# GPSSDver2.net
KiCad netlist of a schematic drawn in EAGLE
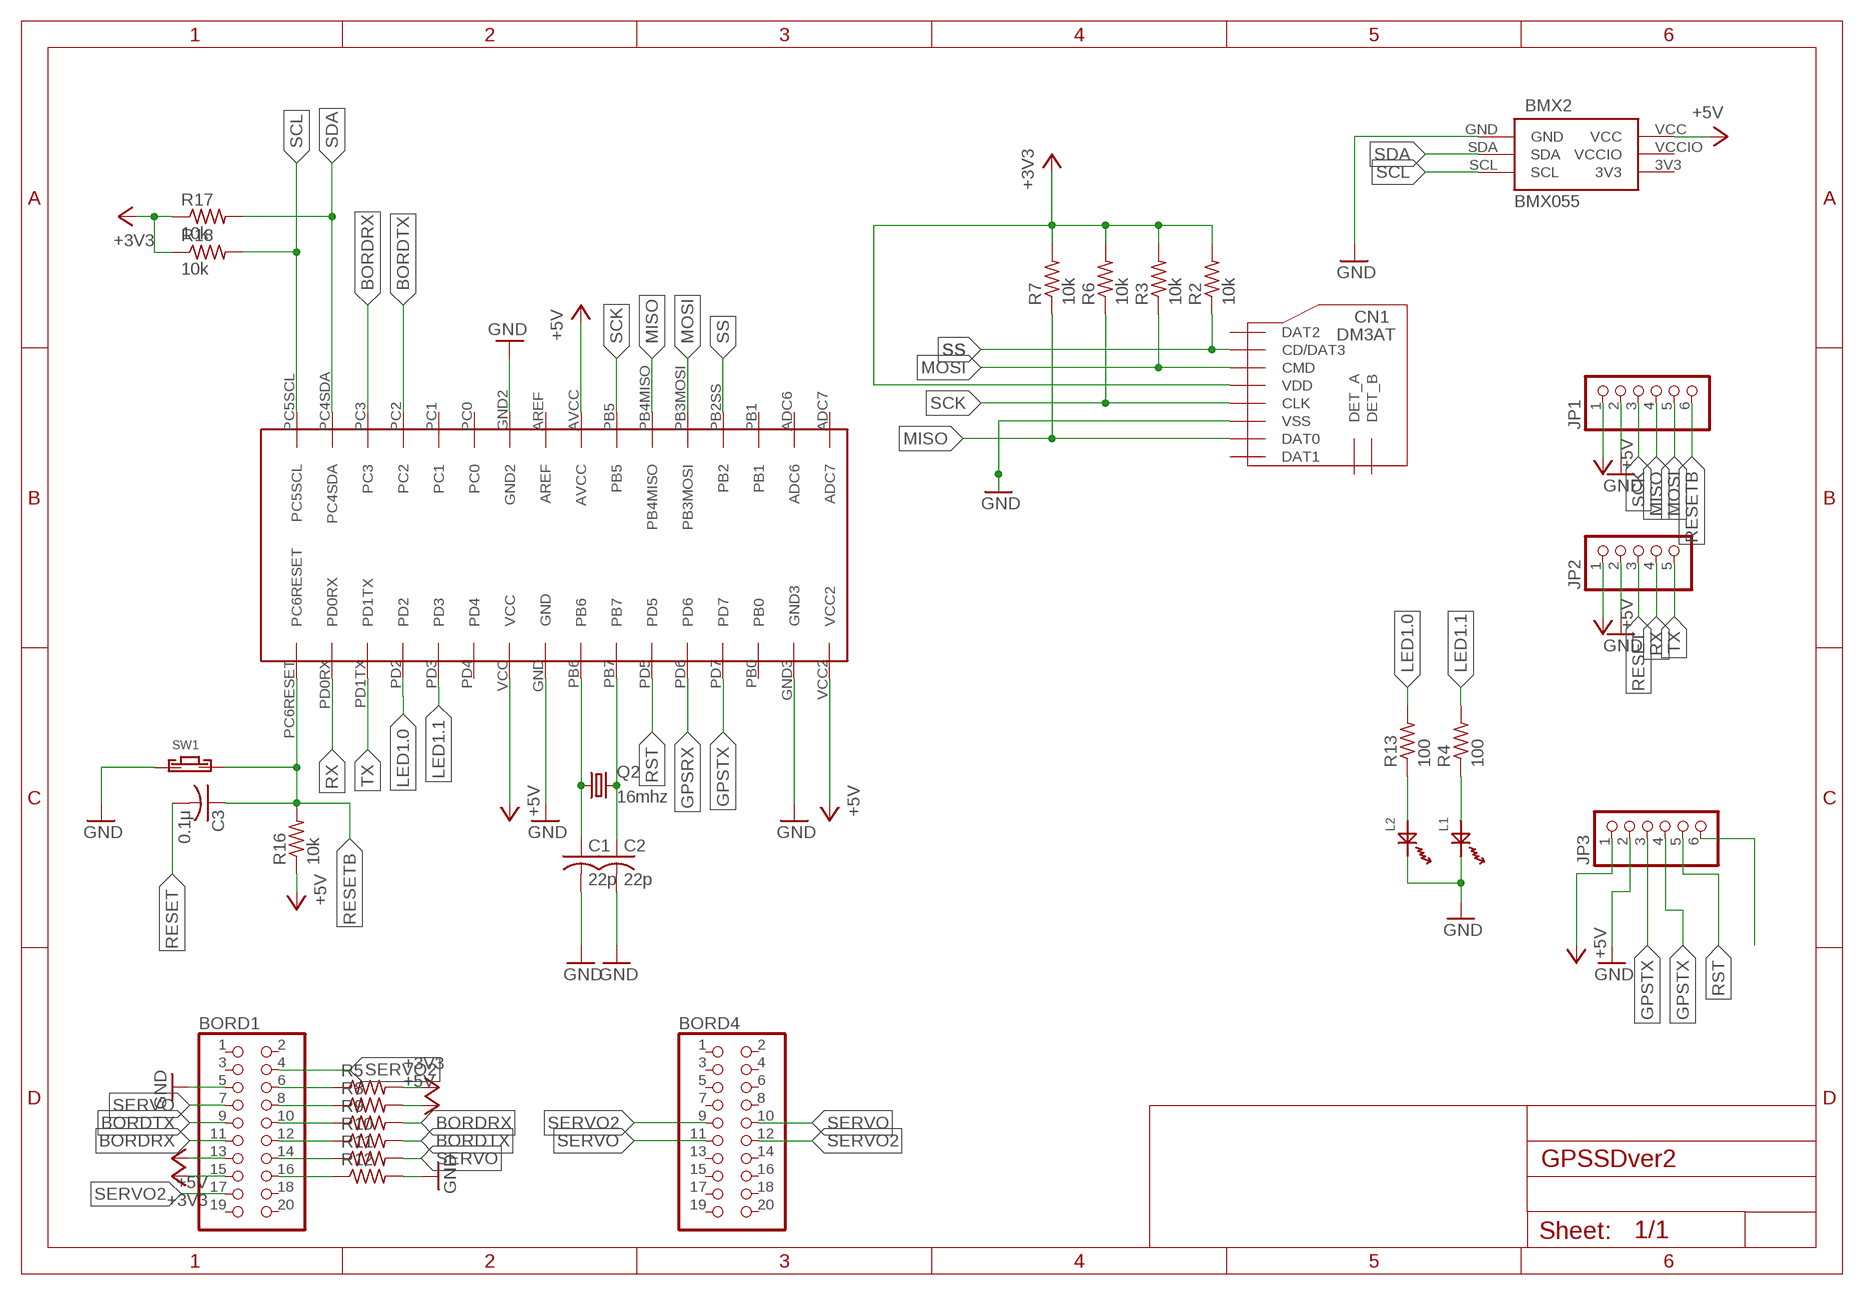
[diagram p0: schematic, sheet 1]

(export (version "E")
  (design (tool "Eeschema 10.0.6"))
  (components
    (comp (ref "BMX2")
      (value "BMX055")
      (footprint "eagle-import:BMX055")
      (libsource (lib "eagle-import") (part "BMX055"))
    )
    (comp (ref "BORD1")
      (value "PINHD-2X10/90")
      (footprint "eagle-import:2X10_90")
      (libsource (lib "eagle-import") (part "PINHD-2X10/90"))
    )
    (comp (ref "BORD4")
      (value "PINHD-2X10/90")
      (footprint "eagle-import:2X10_90")
      (libsource (lib "eagle-import") (part "PINHD-2X10/90"))
    )
    (comp (ref "C1")
      (value "22p")
      (footprint "eagle-import:C1608")
      (libsource (lib "eagle-import") (part "C-USC1608"))
    )
    (comp (ref "C2")
      (value "22p")
      (footprint "eagle-import:C1608")
      (libsource (lib "eagle-import") (part "C-USC1608"))
    )
    (comp (ref "C3")
      (value "0.1μ")
      (footprint "eagle-import:C1608")
      (libsource (lib "eagle-import") (part "C-USC1608"))
    )
    (comp (ref "CN1")
      (value "DM3AT")
      (footprint "eagle-import:DM3AT")
      (libsource (lib "eagle-import") (part "DM3AT"))
    )
    (comp (ref "JP1")
      (value "PINHD-1X6")
      (footprint "eagle-import:1X06")
      (libsource (lib "eagle-import") (part "PINHD-1X6"))
    )
    (comp (ref "JP2")
      (value "PINHD-1X5")
      (footprint "eagle-import:1X05")
      (libsource (lib "eagle-import") (part "PINHD-1X5"))
    )
    (comp (ref "JP3")
      (value "PINHD-1X6")
      (footprint "eagle-import:1X06")
      (libsource (lib "eagle-import") (part "PINHD-1X6"))
    )
    (comp (ref "L1")
      (value "OSXX1608C1A")
      (footprint "eagle-import:OSXX1608C1A")
      (libsource (lib "eagle-import") (part "OSXX1608C1A"))
    )
    (comp (ref "L2")
      (value "OSXX1608C1A")
      (footprint "eagle-import:OSXX1608C1A")
      (libsource (lib "eagle-import") (part "OSXX1608C1A"))
    )
    (comp (ref "Q2")
      (value "16mhz")
      (footprint "eagle-import:HC49UP")
      (libsource (lib "eagle-import") (part "CRYSTALHC49UP"))
    )
    (comp (ref "R2")
      (value "10k")
      (footprint "eagle-import:R0603")
      (libsource (lib "eagle-import") (part "R-US_R0603"))
    )
    (comp (ref "R3")
      (value "10k")
      (footprint "eagle-import:R0603")
      (libsource (lib "eagle-import") (part "R-US_R0603"))
    )
    (comp (ref "R4")
      (value "100")
      (footprint "eagle-import:R0603")
      (libsource (lib "eagle-import") (part "R-US_R0603"))
    )
    (comp (ref "R5")
      (value "R-US_R0603")
      (footprint "eagle-import:R0603")
      (libsource (lib "eagle-import") (part "R-US_R0603"))
    )
    (comp (ref "R6")
      (value "10k")
      (footprint "eagle-import:R0603")
      (libsource (lib "eagle-import") (part "R-US_R0603"))
    )
    (comp (ref "R7")
      (value "10k")
      (footprint "eagle-import:R0603")
      (libsource (lib "eagle-import") (part "R-US_R0603"))
    )
    (comp (ref "R8")
      (value "R-US_R0603")
      (footprint "eagle-import:R0603")
      (libsource (lib "eagle-import") (part "R-US_R0603"))
    )
    (comp (ref "R9")
      (value "R-US_R0603")
      (footprint "eagle-import:R0603")
      (libsource (lib "eagle-import") (part "R-US_R0603"))
    )
    (comp (ref "R10")
      (value "R-US_R0603")
      (footprint "eagle-import:R0603")
      (libsource (lib "eagle-import") (part "R-US_R0603"))
    )
    (comp (ref "R11")
      (value "R-US_R0603")
      (footprint "eagle-import:R0603")
      (libsource (lib "eagle-import") (part "R-US_R0603"))
    )
    (comp (ref "R12")
      (value "R-US_R0603")
      (footprint "eagle-import:R0603")
      (libsource (lib "eagle-import") (part "R-US_R0603"))
    )
    (comp (ref "R13")
      (value "100")
      (footprint "eagle-import:R0603")
      (libsource (lib "eagle-import") (part "R-US_R0603"))
    )
    (comp (ref "R16")
      (value "10k")
      (footprint "eagle-import:R0603")
      (libsource (lib "eagle-import") (part "R-US_R0603"))
    )
    (comp (ref "R17")
      (value "10k")
      (footprint "eagle-import:R0603")
      (libsource (lib "eagle-import") (part "R-US_R0603"))
    )
    (comp (ref "R18")
      (value "10k")
      (footprint "eagle-import:R0603")
      (libsource (lib "eagle-import") (part "R-US_R0603"))
    )
    (comp (ref "SW1")
      (value "TVAF06-A020B-R")
      (footprint "eagle-import:TVAF06-A020B-R")
      (libsource (lib "eagle-import") (part "TVAF06-A020B-R"))
    )
    (comp (ref "U$3")
      (value "ATMEGA328P-AU")
      (footprint "eagle-import:QFP80P900X900X120-32N")
      (libsource (lib "eagle-import") (part "ATMEGA328P-AU"))
    )
  )
  (nets
    (net (code "1") (name "+3V3") (class "Default")
      (node (ref "BORD1") (pin "15") (pinfunction "15_15") (pintype "passive"))
      (node (ref "CN1") (pin "VDD") (pinfunction "VDD_VDD") (pintype "bidirectional"))
      (node (ref "R17") (pin "1") (pinfunction "1_1") (pintype "passive"))
      (node (ref "R18") (pin "1") (pinfunction "1_1") (pintype "passive"))
      (node (ref "R2") (pin "2") (pinfunction "2_2") (pintype "passive"))
      (node (ref "R3") (pin "2") (pinfunction "2_2") (pintype "passive"))
      (node (ref "R5") (pin "2") (pinfunction "2_2") (pintype "passive"))
      (node (ref "R6") (pin "2") (pinfunction "2_2") (pintype "passive"))
      (node (ref "R7") (pin "2") (pinfunction "2_2") (pintype "passive"))
    )
    (net (code "2") (name "+5V") (class "Default")
      (node (ref "BMX2") (pin "VCC") (pinfunction "VCC_VCC") (pintype "power_in"))
      (node (ref "BORD1") (pin "13") (pinfunction "13_13") (pintype "passive"))
      (node (ref "JP1") (pin "1") (pinfunction "1_1") (pintype "passive"))
      (node (ref "JP2") (pin "1") (pinfunction "1_1") (pintype "passive"))
      (node (ref "JP3") (pin "1") (pinfunction "1_1") (pintype "passive"))
      (node (ref "R16") (pin "1") (pinfunction "1_1") (pintype "passive"))
      (node (ref "R8") (pin "2") (pinfunction "2_2") (pintype "passive"))
      (node (ref "U$3") (pin "AVCC") (pinfunction "AVCC_AVCC") (pintype "bidirectional"))
      (node (ref "U$3") (pin "VCC") (pinfunction "VCC_VCC") (pintype "bidirectional"))
      (node (ref "U$3") (pin "VCC2") (pinfunction "VCC2_VCC2") (pintype "bidirectional"))
    )
    (net (code "3") (name "/3V3") (class "Default")
      (node (ref "BMX2") (pin "3V3") (pinfunction "3V3_3V3") (pintype "power_in"))
    )
    (net (code "4") (name "/VCCIO") (class "Default")
      (node (ref "BMX2") (pin "VCCIO") (pinfunction "VCCIO_VCCIO") (pintype "power_in"))
    )
    (net (code "5") (name "BORDRX") (class "Default")
      (node (ref "BORD1") (pin "11") (pinfunction "11_11") (pintype "passive"))
      (node (ref "R9") (pin "2") (pinfunction "2_2") (pintype "passive"))
      (node (ref "U$3") (pin "PC3") (pinfunction "PC3_PC3") (pintype "bidirectional"))
    )
    (net (code "6") (name "BORDTX") (class "Default")
      (node (ref "BORD1") (pin "9") (pinfunction "9_9") (pintype "passive"))
      (node (ref "R10") (pin "2") (pinfunction "2_2") (pintype "passive"))
      (node (ref "U$3") (pin "PC2") (pinfunction "PC2_PC2") (pintype "bidirectional"))
    )
    (net (code "7") (name "GND") (class "Default")
      (node (ref "BMX2") (pin "GND") (pinfunction "GND_GND") (pintype "power_in"))
      (node (ref "BORD1") (pin "5") (pinfunction "5_5") (pintype "passive"))
      (node (ref "C1") (pin "2") (pinfunction "2_2") (pintype "passive"))
      (node (ref "C2") (pin "2") (pinfunction "2_2") (pintype "passive"))
      (node (ref "CN1") (pin "VSS") (pinfunction "VSS_VSS") (pintype "bidirectional"))
      (node (ref "JP1") (pin "2") (pinfunction "2_2") (pintype "passive"))
      (node (ref "JP2") (pin "2") (pinfunction "2_2") (pintype "passive"))
      (node (ref "JP3") (pin "2") (pinfunction "2_2") (pintype "passive"))
      (node (ref "L1") (pin "CT") (pinfunction "CT_CT") (pintype "bidirectional"))
      (node (ref "L2") (pin "CT") (pinfunction "CT_CT") (pintype "bidirectional"))
      (node (ref "R12") (pin "2") (pinfunction "2_2") (pintype "passive"))
      (node (ref "SW1") (pin "P$1") (pinfunction "P$1_P$1") (pintype "bidirectional"))
      (node (ref "U$3") (pin "GND") (pinfunction "GND_GND") (pintype "bidirectional"))
      (node (ref "U$3") (pin "GND2") (pinfunction "GND2_GND2") (pintype "bidirectional"))
      (node (ref "U$3") (pin "GND3") (pinfunction "GND3_GND3") (pintype "bidirectional"))
    )
    (net (code "8") (name "GPSRX") (class "Default")
      (node (ref "U$3") (pin "PD6") (pinfunction "PD6_PD6") (pintype "bidirectional"))
    )
    (net (code "9") (name "GPSTX") (class "Default")
      (node (ref "JP3") (pin "3") (pinfunction "3_3") (pintype "passive"))
      (node (ref "JP3") (pin "4") (pinfunction "4_4") (pintype "passive"))
      (node (ref "U$3") (pin "PD7") (pinfunction "PD7_PD7") (pintype "bidirectional"))
    )
    (net (code "10") (name "LED1.0") (class "Default")
      (node (ref "R13") (pin "2") (pinfunction "2_2") (pintype "passive"))
      (node (ref "U$3") (pin "PD2") (pinfunction "PD2_PD2") (pintype "bidirectional"))
    )
    (net (code "11") (name "LED1.1") (class "Default")
      (node (ref "R4") (pin "2") (pinfunction "2_2") (pintype "passive"))
      (node (ref "U$3") (pin "PD3") (pinfunction "PD3_PD3") (pintype "bidirectional"))
    )
    (net (code "12") (name "MISO") (class "Default")
      (node (ref "CN1") (pin "DAT0") (pinfunction "DAT0_DAT0") (pintype "bidirectional"))
      (node (ref "JP1") (pin "4") (pinfunction "4_4") (pintype "passive"))
      (node (ref "R7") (pin "1") (pinfunction "1_1") (pintype "passive"))
      (node (ref "U$3") (pin "PB4MISO") (pinfunction "PB4MISO_PB4MISO") (pintype "bidirectional"))
    )
    (net (code "13") (name "MOSI") (class "Default")
      (node (ref "CN1") (pin "CMD") (pinfunction "CMD_CMD") (pintype "bidirectional"))
      (node (ref "JP1") (pin "5") (pinfunction "5_5") (pintype "passive"))
      (node (ref "R3") (pin "1") (pinfunction "1_1") (pintype "passive"))
      (node (ref "U$3") (pin "PB3MOSI") (pinfunction "PB3MOSI_PB3MOSI") (pintype "bidirectional"))
    )
    (net (code "14") (name "Net-(BORD1-Pad6)") (class "Default")
      (node (ref "BORD1") (pin "6") (pinfunction "6_6") (pintype "passive"))
      (node (ref "R5") (pin "1") (pinfunction "1_1") (pintype "passive"))
    )
    (net (code "15") (name "Net-(BORD1-Pad8)") (class "Default")
      (node (ref "BORD1") (pin "8") (pinfunction "8_8") (pintype "passive"))
      (node (ref "R8") (pin "1") (pinfunction "1_1") (pintype "passive"))
    )
    (net (code "16") (name "Net-(BORD1-Pad10)") (class "Default")
      (node (ref "BORD1") (pin "10") (pinfunction "10_10") (pintype "passive"))
      (node (ref "R9") (pin "1") (pinfunction "1_1") (pintype "passive"))
    )
    (net (code "17") (name "Net-(BORD1-Pad12)") (class "Default")
      (node (ref "BORD1") (pin "12") (pinfunction "12_12") (pintype "passive"))
      (node (ref "R10") (pin "1") (pinfunction "1_1") (pintype "passive"))
    )
    (net (code "18") (name "Net-(BORD1-Pad14)") (class "Default")
      (node (ref "BORD1") (pin "14") (pinfunction "14_14") (pintype "passive"))
      (node (ref "R11") (pin "1") (pinfunction "1_1") (pintype "passive"))
    )
    (net (code "19") (name "Net-(BORD1-Pad16)") (class "Default")
      (node (ref "BORD1") (pin "16") (pinfunction "16_16") (pintype "passive"))
      (node (ref "R12") (pin "1") (pinfunction "1_1") (pintype "passive"))
    )
    (net (code "20") (name "Net-(C1-Pad1)") (class "Default")
      (node (ref "C1") (pin "1") (pinfunction "1_1") (pintype "passive"))
      (node (ref "Q2") (pin "1") (pinfunction "1_1") (pintype "passive"))
      (node (ref "U$3") (pin "PB6") (pinfunction "PB6_PB6") (pintype "bidirectional"))
    )
    (net (code "21") (name "Net-(C2-Pad1)") (class "Default")
      (node (ref "C2") (pin "1") (pinfunction "1_1") (pintype "passive"))
      (node (ref "Q2") (pin "2") (pinfunction "2_2") (pintype "passive"))
      (node (ref "U$3") (pin "PB7") (pinfunction "PB7_PB7") (pintype "bidirectional"))
    )
    (net (code "22") (name "Net-(L1-PadAN)") (class "Default")
      (node (ref "L1") (pin "AN") (pinfunction "AN_AN") (pintype "bidirectional"))
      (node (ref "R4") (pin "1") (pinfunction "1_1") (pintype "passive"))
    )
    (net (code "23") (name "Net-(L2-PadAN)") (class "Default")
      (node (ref "L2") (pin "AN") (pinfunction "AN_AN") (pintype "bidirectional"))
      (node (ref "R13") (pin "1") (pinfunction "1_1") (pintype "passive"))
    )
    (net (code "24") (name "RESET") (class "Default")
      (node (ref "C3") (pin "2") (pinfunction "2_2") (pintype "passive"))
      (node (ref "JP2") (pin "3") (pinfunction "3_3") (pintype "passive"))
    )
    (net (code "25") (name "RESETB") (class "Default")
      (node (ref "C3") (pin "1") (pinfunction "1_1") (pintype "passive"))
      (node (ref "JP1") (pin "6") (pinfunction "6_6") (pintype "passive"))
      (node (ref "R16") (pin "2") (pinfunction "2_2") (pintype "passive"))
      (node (ref "SW1") (pin "P$2") (pinfunction "P$2_P$2") (pintype "bidirectional"))
      (node (ref "U$3") (pin "PC6RESET") (pinfunction "PC6RESET_PC6RESET") (pintype "bidirectional"))
    )
    (net (code "26") (name "RST") (class "Default")
      (node (ref "JP3") (pin "5") (pinfunction "5_5") (pintype "passive"))
      (node (ref "U$3") (pin "PD5") (pinfunction "PD5_PD5") (pintype "bidirectional"))
    )
    (net (code "27") (name "RX") (class "Default")
      (node (ref "JP2") (pin "4") (pinfunction "4_4") (pintype "passive"))
      (node (ref "U$3") (pin "PD0RX") (pinfunction "PD0RX_PD0RX") (pintype "bidirectional"))
    )
    (net (code "28") (name "SCK") (class "Default")
      (node (ref "CN1") (pin "CLK") (pinfunction "CLK_CLK") (pintype "bidirectional"))
      (node (ref "JP1") (pin "3") (pinfunction "3_3") (pintype "passive"))
      (node (ref "R6") (pin "1") (pinfunction "1_1") (pintype "passive"))
      (node (ref "U$3") (pin "PB5") (pinfunction "PB5_PB5") (pintype "bidirectional"))
    )
    (net (code "29") (name "SCL") (class "Default")
      (node (ref "BMX2") (pin "SCL") (pinfunction "SCL_SCL") (pintype "bidirectional"))
      (node (ref "R18") (pin "2") (pinfunction "2_2") (pintype "passive"))
      (node (ref "U$3") (pin "PC5SCL") (pinfunction "PC5SCL_PC5SCL") (pintype "bidirectional"))
    )
    (net (code "30") (name "SDA") (class "Default")
      (node (ref "BMX2") (pin "SDA") (pinfunction "SDA_SDA") (pintype "bidirectional"))
      (node (ref "R17") (pin "2") (pinfunction "2_2") (pintype "passive"))
      (node (ref "U$3") (pin "PC4SDA") (pinfunction "PC4SDA_PC4SDA") (pintype "bidirectional"))
    )
    (net (code "31") (name "SERVO") (class "Default")
      (node (ref "BORD1") (pin "7") (pinfunction "7_7") (pintype "passive"))
      (node (ref "BORD4") (pin "10") (pinfunction "10_10") (pintype "passive"))
      (node (ref "BORD4") (pin "11") (pinfunction "11_11") (pintype "passive"))
      (node (ref "R11") (pin "2") (pinfunction "2_2") (pintype "passive"))
    )
    (net (code "32") (name "SERVO2") (class "Default")
      (node (ref "BORD1") (pin "17") (pinfunction "17_17") (pintype "passive"))
      (node (ref "BORD1") (pin "4") (pinfunction "4_4") (pintype "passive"))
      (node (ref "BORD4") (pin "12") (pinfunction "12_12") (pintype "passive"))
      (node (ref "BORD4") (pin "9") (pinfunction "9_9") (pintype "passive"))
    )
    (net (code "33") (name "SS") (class "Default")
      (node (ref "CN1") (pin "CD/DAT3") (pinfunction "CD/DAT3_CD/DAT3") (pintype "bidirectional"))
      (node (ref "R2") (pin "1") (pinfunction "1_1") (pintype "passive"))
      (node (ref "U$3") (pin "PB2SS") (pinfunction "PB2_PB2SS") (pintype "bidirectional"))
    )
    (net (code "34") (name "TX") (class "Default")
      (node (ref "JP2") (pin "5") (pinfunction "5_5") (pintype "passive"))
      (node (ref "U$3") (pin "PD1TX") (pinfunction "PD1TX_PD1TX") (pintype "bidirectional"))
    )
    (net (code "35") (name "unconnected-(BORD1-Pad1)") (class "Default")
      (node (ref "BORD1") (pin "1") (pinfunction "1_1") (pintype "passive"))
    )
    (net (code "36") (name "unconnected-(BORD1-Pad2)") (class "Default")
      (node (ref "BORD1") (pin "2") (pinfunction "2_2") (pintype "passive"))
    )
    (net (code "37") (name "unconnected-(BORD1-Pad3)") (class "Default")
      (node (ref "BORD1") (pin "3") (pinfunction "3_3") (pintype "passive"))
    )
    (net (code "38") (name "unconnected-(BORD1-Pad18)") (class "Default")
      (node (ref "BORD1") (pin "18") (pinfunction "18_18") (pintype "passive"))
    )
    (net (code "39") (name "unconnected-(BORD1-Pad19)") (class "Default")
      (node (ref "BORD1") (pin "19") (pinfunction "19_19") (pintype "passive"))
    )
    (net (code "40") (name "unconnected-(BORD1-Pad20)") (class "Default")
      (node (ref "BORD1") (pin "20") (pinfunction "20_20") (pintype "passive"))
    )
    (net (code "41") (name "unconnected-(BORD4-Pad1)") (class "Default")
      (node (ref "BORD4") (pin "1") (pinfunction "1_1") (pintype "passive"))
    )
    (net (code "42") (name "unconnected-(BORD4-Pad2)") (class "Default")
      (node (ref "BORD4") (pin "2") (pinfunction "2_2") (pintype "passive"))
    )
    (net (code "43") (name "unconnected-(BORD4-Pad3)") (class "Default")
      (node (ref "BORD4") (pin "3") (pinfunction "3_3") (pintype "passive"))
    )
    (net (code "44") (name "unconnected-(BORD4-Pad4)") (class "Default")
      (node (ref "BORD4") (pin "4") (pinfunction "4_4") (pintype "passive"))
    )
    (net (code "45") (name "unconnected-(BORD4-Pad5)") (class "Default")
      (node (ref "BORD4") (pin "5") (pinfunction "5_5") (pintype "passive"))
    )
    (net (code "46") (name "unconnected-(BORD4-Pad6)") (class "Default")
      (node (ref "BORD4") (pin "6") (pinfunction "6_6") (pintype "passive"))
    )
    (net (code "47") (name "unconnected-(BORD4-Pad7)") (class "Default")
      (node (ref "BORD4") (pin "7") (pinfunction "7_7") (pintype "passive"))
    )
    (net (code "48") (name "unconnected-(BORD4-Pad8)") (class "Default")
      (node (ref "BORD4") (pin "8") (pinfunction "8_8") (pintype "passive"))
    )
    (net (code "49") (name "unconnected-(BORD4-Pad13)") (class "Default")
      (node (ref "BORD4") (pin "13") (pinfunction "13_13") (pintype "passive"))
    )
    (net (code "50") (name "unconnected-(BORD4-Pad14)") (class "Default")
      (node (ref "BORD4") (pin "14") (pinfunction "14_14") (pintype "passive"))
    )
    (net (code "51") (name "unconnected-(BORD4-Pad15)") (class "Default")
      (node (ref "BORD4") (pin "15") (pinfunction "15_15") (pintype "passive"))
    )
    (net (code "52") (name "unconnected-(BORD4-Pad16)") (class "Default")
      (node (ref "BORD4") (pin "16") (pinfunction "16_16") (pintype "passive"))
    )
    (net (code "53") (name "unconnected-(BORD4-Pad17)") (class "Default")
      (node (ref "BORD4") (pin "17") (pinfunction "17_17") (pintype "passive"))
    )
    (net (code "54") (name "unconnected-(BORD4-Pad18)") (class "Default")
      (node (ref "BORD4") (pin "18") (pinfunction "18_18") (pintype "passive"))
    )
    (net (code "55") (name "unconnected-(BORD4-Pad19)") (class "Default")
      (node (ref "BORD4") (pin "19") (pinfunction "19_19") (pintype "passive"))
    )
    (net (code "56") (name "unconnected-(BORD4-Pad20)") (class "Default")
      (node (ref "BORD4") (pin "20") (pinfunction "20_20") (pintype "passive"))
    )
    (net (code "57") (name "unconnected-(CN1-PadDAT1)") (class "Default")
      (node (ref "CN1") (pin "DAT1") (pinfunction "DAT1_DAT1") (pintype "bidirectional"))
    )
    (net (code "58") (name "unconnected-(CN1-PadDAT2)") (class "Default")
      (node (ref "CN1") (pin "DAT2") (pinfunction "DAT2_DAT2") (pintype "bidirectional"))
    )
    (net (code "59") (name "unconnected-(CN1-PadDET_A)") (class "Default")
      (node (ref "CN1") (pin "DET_A") (pinfunction "DET_A_DET_A") (pintype "bidirectional"))
    )
    (net (code "60") (name "unconnected-(CN1-PadDET_B)") (class "Default")
      (node (ref "CN1") (pin "DET_B") (pinfunction "DET_B_DET_B") (pintype "bidirectional"))
    )
    (net (code "61") (name "unconnected-(JP3-Pad6)") (class "Default")
      (node (ref "JP3") (pin "6") (pinfunction "6_6") (pintype "passive"))
    )
    (net (code "62") (name "unconnected-(U$3-PadADC6)") (class "Default")
      (node (ref "U$3") (pin "ADC6") (pinfunction "ADC6_ADC6") (pintype "bidirectional"))
    )
    (net (code "63") (name "unconnected-(U$3-PadADC7)") (class "Default")
      (node (ref "U$3") (pin "ADC7") (pinfunction "ADC7_ADC7") (pintype "bidirectional"))
    )
    (net (code "64") (name "unconnected-(U$3-PadAREF)") (class "Default")
      (node (ref "U$3") (pin "AREF") (pinfunction "AREF_AREF") (pintype "bidirectional"))
    )
    (net (code "65") (name "unconnected-(U$3-PadPB0)") (class "Default")
      (node (ref "U$3") (pin "PB0") (pinfunction "PB0_PB0") (pintype "bidirectional"))
    )
    (net (code "66") (name "unconnected-(U$3-PadPB1)") (class "Default")
      (node (ref "U$3") (pin "PB1") (pinfunction "PB1_PB1") (pintype "bidirectional"))
    )
    (net (code "67") (name "unconnected-(U$3-PadPC0)") (class "Default")
      (node (ref "U$3") (pin "PC0") (pinfunction "PC0_PC0") (pintype "bidirectional"))
    )
    (net (code "68") (name "unconnected-(U$3-PadPC1)") (class "Default")
      (node (ref "U$3") (pin "PC1") (pinfunction "PC1_PC1") (pintype "bidirectional"))
    )
    (net (code "69") (name "unconnected-(U$3-PadPD4)") (class "Default")
      (node (ref "U$3") (pin "PD4") (pinfunction "PD4_PD4") (pintype "bidirectional"))
    )
  )
)
